# Instrumentation_amplifier_MSP430FR2355.net
KiCad netlist of a schematic drawn in EAGLE
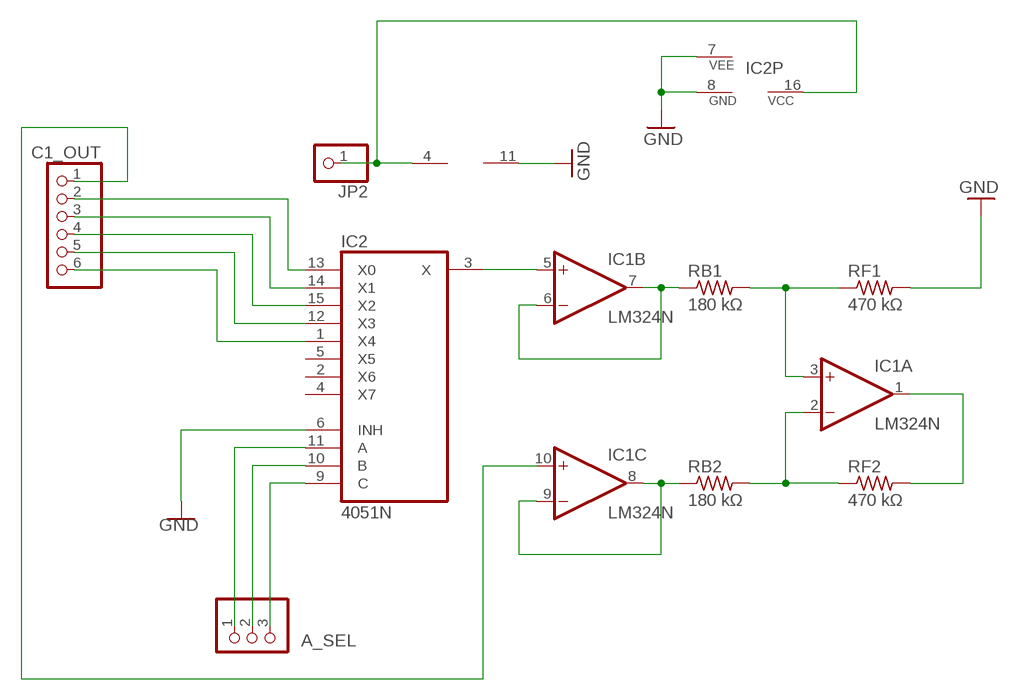
[diagram p0: schematic, sheet 1]

(export (version "E")
  (design (tool "Eeschema 10.0.6"))
  (components
    (comp (ref "A_SEL")
      (value "PINHD-1X3")
      (footprint "eagle-import:1X03")
      (libsource (lib "eagle-import") (part "PINHD-1X3"))
    )
    (comp (ref "C1_OUT")
      (value "PINHD-1X6")
      (footprint "eagle-import:1X06")
      (libsource (lib "eagle-import") (part "PINHD-1X6"))
    )
    (comp (ref "IC1")
      (value "LM324N")
      (footprint "eagle-import:DIL14")
      (libsource (lib "eagle-import") (part "LM324N"))
    )
    (comp (ref "IC2")
      (value "4051N")
      (footprint "eagle-import:DIL16")
      (libsource (lib "eagle-import") (part "4051N"))
    )
    (comp (ref "JP2")
      (value "PINHD-1X1")
      (footprint "eagle-import:1X01")
      (libsource (lib "eagle-import") (part "PINHD-1X1"))
    )
    (comp (ref "RB1")
      (value "180 kΩ")
      (footprint "eagle-import:0204_7")
      (libsource (lib "eagle-import") (part "R-US_0204/7"))
    )
    (comp (ref "RB2")
      (value "180 kΩ")
      (footprint "eagle-import:0204_7")
      (libsource (lib "eagle-import") (part "R-US_0204/7"))
    )
    (comp (ref "RF1")
      (value "470 kΩ")
      (footprint "eagle-import:0204_7")
      (libsource (lib "eagle-import") (part "R-US_0204/7"))
    )
    (comp (ref "RF2")
      (value "470 kΩ")
      (footprint "eagle-import:0204_7")
      (libsource (lib "eagle-import") (part "R-US_0204/7"))
    )
  )
  (nets
    (net (code "1") (name "GND") (class "Default")
      (node (ref "IC1") (pin "11") (pinfunction "V-_11") (pintype "power_in"))
      (node (ref "IC2") (pin "6") (pinfunction "INH_6") (pintype "input"))
      (node (ref "IC2") (pin "7") (pinfunction "VEE_7") (pintype "power_in"))
      (node (ref "IC2") (pin "8") (pinfunction "GND_8") (pintype "power_in"))
      (node (ref "RF1") (pin "2") (pinfunction "2_2") (pintype "passive"))
    )
    (net (code "2") (name "Net-(IC1A-+IN)") (class "Default")
      (node (ref "IC1") (pin "3") (pinfunction "+IN_3") (pintype "input"))
      (node (ref "RB1") (pin "2") (pinfunction "2_2") (pintype "passive"))
      (node (ref "RF1") (pin "1") (pinfunction "1_1") (pintype "passive"))
    )
    (net (code "3") (name "Net-(IC1A--IN)") (class "Default")
      (node (ref "IC1") (pin "2") (pinfunction "-IN_2") (pintype "input"))
      (node (ref "RB2") (pin "2") (pinfunction "2_2") (pintype "passive"))
      (node (ref "RF2") (pin "1") (pinfunction "1_1") (pintype "passive"))
    )
    (net (code "4") (name "Net-(IC1A-OUT)") (class "Default")
      (node (ref "IC1") (pin "1") (pinfunction "OUT_1") (pintype "output"))
      (node (ref "RF2") (pin "2") (pinfunction "2_2") (pintype "passive"))
    )
    (net (code "5") (name "Net-(IC1B-+IN)") (class "Default")
      (node (ref "IC1") (pin "5") (pinfunction "+IN_5") (pintype "input"))
      (node (ref "IC2") (pin "3") (pinfunction "X_3") (pintype "bidirectional"))
    )
    (net (code "6") (name "Net-(IC1B--IN)") (class "Default")
      (node (ref "IC1") (pin "6") (pinfunction "-IN_6") (pintype "input"))
      (node (ref "IC1") (pin "7") (pinfunction "OUT_7") (pintype "output"))
      (node (ref "RB1") (pin "1") (pinfunction "1_1") (pintype "passive"))
    )
    (net (code "7") (name "Net-(IC1C-+IN)") (class "Default")
      (node (ref "C1_OUT") (pin "1") (pinfunction "1_1") (pintype "passive"))
      (node (ref "IC1") (pin "10") (pinfunction "+IN_10") (pintype "input"))
    )
    (net (code "8") (name "Net-(IC1C--IN)") (class "Default")
      (node (ref "IC1") (pin "8") (pinfunction "OUT_8") (pintype "output"))
      (node (ref "IC1") (pin "9") (pinfunction "-IN_9") (pintype "input"))
      (node (ref "RB2") (pin "1") (pinfunction "1_1") (pintype "passive"))
    )
    (net (code "9") (name "Net-(IC1E-V+)") (class "Default")
      (node (ref "IC1") (pin "4") (pinfunction "V+_4") (pintype "power_in"))
      (node (ref "IC2") (pin "16") (pinfunction "VCC_16") (pintype "power_in"))
      (node (ref "JP2") (pin "1") (pinfunction "1_1") (pintype "passive"))
    )
    (net (code "10") (name "Net-(IC2A-A)") (class "Default")
      (node (ref "A_SEL") (pin "1") (pinfunction "1_1") (pintype "passive"))
      (node (ref "IC2") (pin "11") (pinfunction "A_11") (pintype "input"))
    )
    (net (code "11") (name "Net-(IC2A-B)") (class "Default")
      (node (ref "A_SEL") (pin "2") (pinfunction "2_2") (pintype "passive"))
      (node (ref "IC2") (pin "10") (pinfunction "B_10") (pintype "input"))
    )
    (net (code "12") (name "Net-(IC2A-C)") (class "Default")
      (node (ref "A_SEL") (pin "3") (pinfunction "3_3") (pintype "passive"))
      (node (ref "IC2") (pin "9") (pinfunction "C_9") (pintype "input"))
    )
    (net (code "13") (name "Net-(IC2A-X0)") (class "Default")
      (node (ref "C1_OUT") (pin "2") (pinfunction "2_2") (pintype "passive"))
      (node (ref "IC2") (pin "13") (pinfunction "X0_13") (pintype "bidirectional"))
    )
    (net (code "14") (name "Net-(IC2A-X1)") (class "Default")
      (node (ref "C1_OUT") (pin "3") (pinfunction "3_3") (pintype "passive"))
      (node (ref "IC2") (pin "14") (pinfunction "X1_14") (pintype "bidirectional"))
    )
    (net (code "15") (name "Net-(IC2A-X2)") (class "Default")
      (node (ref "C1_OUT") (pin "4") (pinfunction "4_4") (pintype "passive"))
      (node (ref "IC2") (pin "15") (pinfunction "X2_15") (pintype "bidirectional"))
    )
    (net (code "16") (name "Net-(IC2A-X3)") (class "Default")
      (node (ref "C1_OUT") (pin "5") (pinfunction "5_5") (pintype "passive"))
      (node (ref "IC2") (pin "12") (pinfunction "X3_12") (pintype "bidirectional"))
    )
    (net (code "17") (name "Net-(IC2A-X4)") (class "Default")
      (node (ref "C1_OUT") (pin "6") (pinfunction "6_6") (pintype "passive"))
      (node (ref "IC2") (pin "1") (pinfunction "X4_1") (pintype "bidirectional"))
    )
    (net (code "18") (name "unconnected-(IC2A-X5-Pad5)") (class "Default")
      (node (ref "IC2") (pin "5") (pinfunction "X5_5") (pintype "bidirectional"))
    )
    (net (code "19") (name "unconnected-(IC2A-X6-Pad2)") (class "Default")
      (node (ref "IC2") (pin "2") (pinfunction "X6_2") (pintype "bidirectional"))
    )
    (net (code "20") (name "unconnected-(IC2A-X7-Pad4)") (class "Default")
      (node (ref "IC2") (pin "4") (pinfunction "X7_4") (pintype "bidirectional"))
    )
  )
)
